# nav.net
KiCad netlist of a schematic drawn in EAGLE
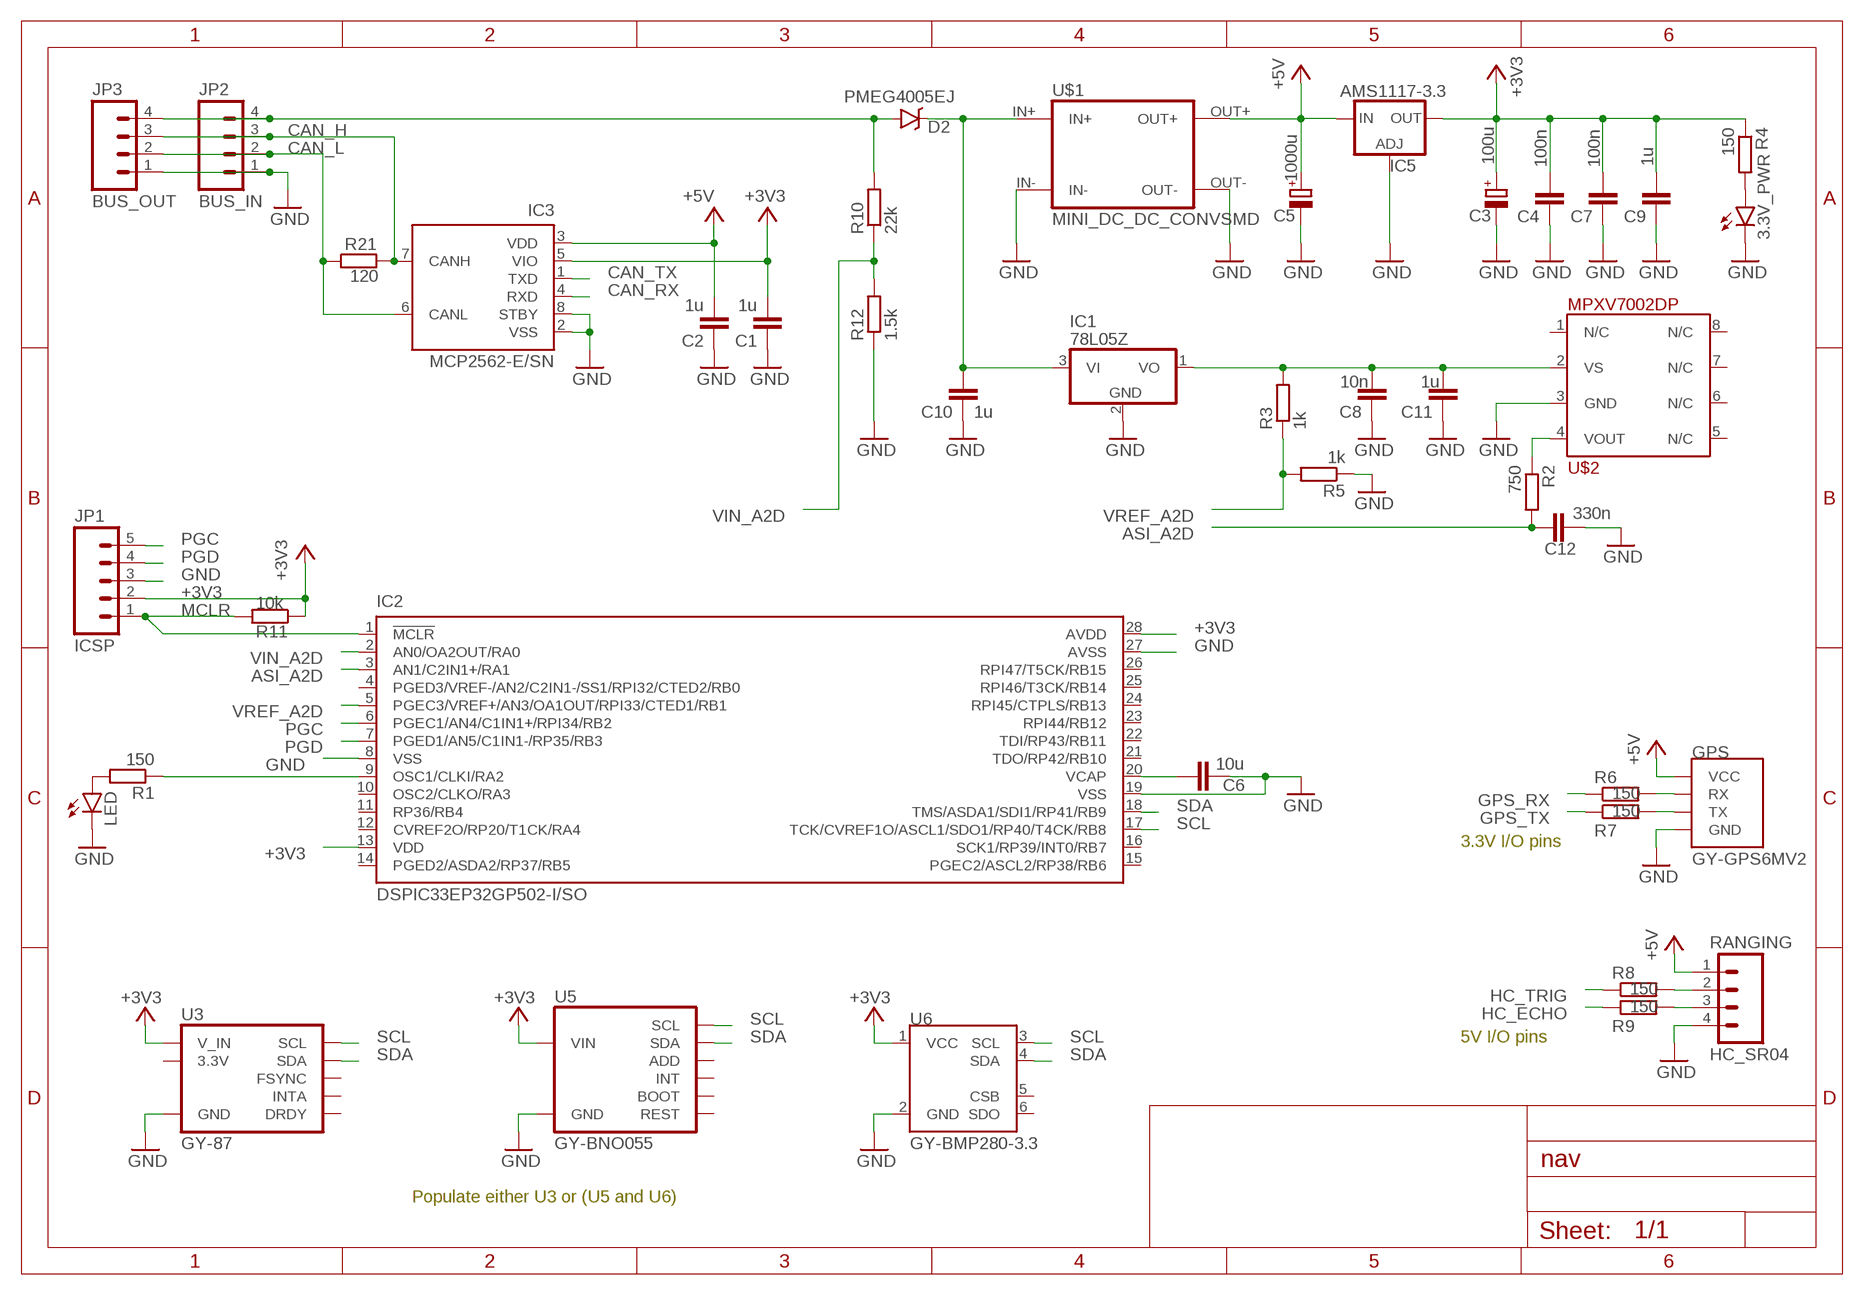
[diagram p0: schematic, sheet 1]

(export (version "E")
  (design (tool "Eeschema 10.0.6"))
  (components
    (comp (ref "3.3V_PWR")
      (value "LED-FKIT-1206")
      (footprint "eagle-import:FKIT-LED-1206")
      (libsource (lib "eagle-import") (part "LED-FKIT-1206"))
    )
    (comp (ref "C1")
      (value "1u")
      (footprint "eagle-import:C0603K")
      (libsource (lib "eagle-import") (part "C-EUC0603K"))
    )
    (comp (ref "C2")
      (value "1u")
      (footprint "eagle-import:C0603K")
      (libsource (lib "eagle-import") (part "C-EUC0603K"))
    )
    (comp (ref "C3")
      (value "100u")
      (footprint "eagle-import:E2,5-7")
      (libsource (lib "eagle-import") (part "CPOL-EUE2.5-7"))
    )
    (comp (ref "C4")
      (value "100n")
      (footprint "eagle-import:C0603K")
      (libsource (lib "eagle-import") (part "C-EUC0603K"))
    )
    (comp (ref "C5")
      (value "1000u")
      (footprint "eagle-import:E3,5-8")
      (libsource (lib "eagle-import") (part "CPOL-EUE3.5-8"))
    )
    (comp (ref "C6")
      (value "10u")
      (footprint "eagle-import:C0805K")
      (libsource (lib "eagle-import") (part "C-EUC0805K"))
    )
    (comp (ref "C7")
      (value "100n")
      (footprint "eagle-import:C0603K")
      (libsource (lib "eagle-import") (part "C-EUC0603K"))
    )
    (comp (ref "C8")
      (value "10n")
      (footprint "eagle-import:C0603K")
      (libsource (lib "eagle-import") (part "C-EUC0603K"))
    )
    (comp (ref "C9")
      (value "1u")
      (footprint "eagle-import:C0603")
      (libsource (lib "eagle-import") (part "C-EUC0603"))
    )
    (comp (ref "C10")
      (value "1u")
      (footprint "eagle-import:C0603")
      (libsource (lib "eagle-import") (part "C-EUC0603"))
    )
    (comp (ref "C11")
      (value "1u")
      (footprint "eagle-import:C0603K")
      (libsource (lib "eagle-import") (part "C-EUC0603K"))
    )
    (comp (ref "C12")
      (value "330n")
      (footprint "eagle-import:C0603K")
      (libsource (lib "eagle-import") (part "C-EUC0603K"))
    )
    (comp (ref "D2")
      (value "PMEG4005EJ")
      (footprint "eagle-import:SOD-323")
      (libsource (lib "eagle-import") (part "DIODE-SCHOTTKY-PMEG4005EJ"))
    )
    (comp (ref "GPS")
      (value "GY-GPS6MV2")
      (footprint "eagle-import:GY-GPS6MV2")
      (libsource (lib "eagle-import") (part "GY-GPS6MV2"))
    )
    (comp (ref "IC1")
      (value "78L05Z")
      (footprint "eagle-import:TO92")
      (libsource (lib "eagle-import") (part "78ZL05"))
    )
    (comp (ref "IC2")
      (value "DSPIC33EP32GP502-I/SO")
      (footprint "eagle-import:SO28W")
      (libsource (lib "eagle-import") (part "DSPIC33EP502?-I/SO32GP"))
    )
    (comp (ref "IC3")
      (value "MCP2562-E/SN")
      (footprint "eagle-import:SO-08")
      (libsource (lib "eagle-import") (part "MCP2562-E/SN"))
    )
    (comp (ref "IC5")
      (value "AMS1117-3.3")
      (footprint "eagle-import:SOT223")
      (libsource (lib "eagle-import") (part "LD117A?S33TR"))
    )
    (comp (ref "JP1")
      (value "ICSP")
      (footprint "eagle-import:1X05")
      (libsource (lib "eagle-import") (part "M05PTH"))
    )
    (comp (ref "JP2")
      (value "BUS_IN")
      (footprint "eagle-import:1X04")
      (libsource (lib "eagle-import") (part "M04PTH"))
    )
    (comp (ref "JP3")
      (value "BUS_OUT")
      (footprint "eagle-import:1X04")
      (libsource (lib "eagle-import") (part "M04PTH"))
    )
    (comp (ref "LED")
      (value "LED-FKIT-1206")
      (footprint "eagle-import:FKIT-LED-1206")
      (libsource (lib "eagle-import") (part "LED-FKIT-1206"))
    )
    (comp (ref "R1")
      (value "150")
      (footprint "eagle-import:R0603")
      (libsource (lib "eagle-import") (part "R-EU_R0603"))
    )
    (comp (ref "R2")
      (value "750")
      (footprint "eagle-import:R0603")
      (libsource (lib "eagle-import") (part "R-EU_R0603"))
    )
    (comp (ref "R3")
      (value "1k")
      (footprint "eagle-import:R0603")
      (libsource (lib "eagle-import") (part "R-EU_R0603"))
    )
    (comp (ref "R4")
      (value "150")
      (footprint "eagle-import:R0603")
      (libsource (lib "eagle-import") (part "R-EU_R0603"))
    )
    (comp (ref "R5")
      (value "1k")
      (footprint "eagle-import:R0603")
      (libsource (lib "eagle-import") (part "R-EU_R0603"))
    )
    (comp (ref "R6")
      (value "150")
      (footprint "eagle-import:R0603")
      (libsource (lib "eagle-import") (part "R-EU_R0603"))
    )
    (comp (ref "R7")
      (value "150")
      (footprint "eagle-import:R0603")
      (libsource (lib "eagle-import") (part "R-EU_R0603"))
    )
    (comp (ref "R8")
      (value "150")
      (footprint "eagle-import:R0603")
      (libsource (lib "eagle-import") (part "R-EU_R0603"))
    )
    (comp (ref "R9")
      (value "150")
      (footprint "eagle-import:R0603")
      (libsource (lib "eagle-import") (part "R-EU_R0603"))
    )
    (comp (ref "R10")
      (value "22k")
      (footprint "eagle-import:R0603")
      (libsource (lib "eagle-import") (part "R-EU_R0603"))
    )
    (comp (ref "R11")
      (value "10k")
      (footprint "eagle-import:R0603")
      (libsource (lib "eagle-import") (part "R-EU_R0603"))
    )
    (comp (ref "R12")
      (value "1.5k")
      (footprint "eagle-import:R0603")
      (libsource (lib "eagle-import") (part "R-EU_R0603"))
    )
    (comp (ref "R21")
      (value "120")
      (footprint "eagle-import:R0603")
      (libsource (lib "eagle-import") (part "R-EU_R0603"))
    )
    (comp (ref "RANGING")
      (value "HC_SR04")
      (footprint "eagle-import:1X04")
      (libsource (lib "eagle-import") (part "M04PTH"))
    )
    (comp (ref "U$1")
      (value "MINI_DC_DC_CONVSMD")
      (footprint "eagle-import:DSN-MINI-360-SMD")
      (libsource (lib "eagle-import") (part "MINI_DC_DC_CONVSMD"))
    )
    (comp (ref "U$2")
      (value "MPXV7002DP")
      (footprint "eagle-import:MPXV7002DP")
      (libsource (lib "eagle-import") (part "MPXV7002DP"))
    )
    (comp (ref "U3")
      (value "GY-87")
      (footprint "eagle-import:GY-87")
      (libsource (lib "eagle-import") (part "GY-87"))
    )
    (comp (ref "U5")
      (value "GY-BNO055")
      (footprint "eagle-import:GY-BNO055")
      (libsource (lib "eagle-import") (part "GY-BNO055"))
    )
    (comp (ref "U6")
      (value "GY-BMP280-3.3")
      (footprint "eagle-import:GY-BMP280-3.3")
      (libsource (lib "eagle-import") (part "GY-BMP280-3.3"))
    )
  )
  (nets
    (net (code "1") (name "+3V3") (class "Default")
      (node (ref "C1") (pin "2") (pinfunction "2_2") (pintype "passive"))
      (node (ref "C3") (pin "+") (pinfunction "+_+") (pintype "passive"))
      (node (ref "C4") (pin "2") (pinfunction "2_2") (pintype "passive"))
      (node (ref "C7") (pin "2") (pinfunction "2_2") (pintype "passive"))
      (node (ref "C9") (pin "2") (pinfunction "2_2") (pintype "passive"))
      (node (ref "IC2") (pin "13") (pinfunction "VDD_13") (pintype "power_in"))
      (node (ref "IC2") (pin "28") (pinfunction "AVDD_28") (pintype "power_in"))
      (node (ref "IC3") (pin "5") (pinfunction "VIO_5") (pintype "power_in"))
      (node (ref "IC5") (pin "2") (pinfunction "OUT_2") (pintype "passive"))
      (node (ref "IC5") (pin "@2") (pinfunction "OUT_@2") (pintype "passive"))
      (node (ref "JP1") (pin "2") (pinfunction "2_2") (pintype "passive"))
      (node (ref "R11") (pin "1") (pinfunction "1_1") (pintype "passive"))
      (node (ref "R4") (pin "1") (pinfunction "1_1") (pintype "passive"))
      (node (ref "U3") (pin "VCC_IN") (pinfunction "V_IN_VCC_IN") (pintype "power_in"))
      (node (ref "U5") (pin "VIN") (pinfunction "VIN_VIN") (pintype "power_in"))
      (node (ref "U6") (pin "1") (pinfunction "VCC_1") (pintype "bidirectional"))
    )
    (net (code "2") (name "+5V") (class "Default")
      (node (ref "C2") (pin "2") (pinfunction "2_2") (pintype "passive"))
      (node (ref "C5") (pin "+") (pinfunction "+_+") (pintype "passive"))
      (node (ref "GPS") (pin "VCC") (pinfunction "VCC_VCC") (pintype "power_in"))
      (node (ref "IC3") (pin "3") (pinfunction "VDD_3") (pintype "power_in"))
      (node (ref "IC5") (pin "3") (pinfunction "IN_3") (pintype "input"))
      (node (ref "RANGING") (pin "1") (pinfunction "1_1") (pintype "passive"))
      (node (ref "U$1") (pin "OUT+") (pinfunction "OUT+_OUT+") (pintype "output"))
    )
    (net (code "3") (name "/3.3V") (class "Default")
      (node (ref "U3") (pin "3.3V") (pinfunction "3.3V_3.3V") (pintype "power_in"))
    )
    (net (code "4") (name "/ASI_A2D") (class "Default")
      (node (ref "C12") (pin "2") (pinfunction "2_2") (pintype "passive"))
      (node (ref "IC2") (pin "3") (pinfunction "AN1/C2IN1+/RA1_3") (pintype "bidirectional"))
      (node (ref "R2") (pin "2") (pinfunction "2_2") (pintype "passive"))
    )
    (net (code "5") (name "/CAN_H") (class "Default")
      (node (ref "IC3") (pin "7") (pinfunction "CANH_7") (pintype "bidirectional"))
      (node (ref "JP2") (pin "3") (pinfunction "3_3") (pintype "passive"))
      (node (ref "JP3") (pin "3") (pinfunction "3_3") (pintype "passive"))
      (node (ref "R21") (pin "2") (pinfunction "2_2") (pintype "passive"))
    )
    (net (code "6") (name "/CAN_L") (class "Default")
      (node (ref "IC3") (pin "6") (pinfunction "CANL_6") (pintype "bidirectional"))
      (node (ref "JP2") (pin "2") (pinfunction "2_2") (pintype "passive"))
      (node (ref "JP3") (pin "2") (pinfunction "2_2") (pintype "passive"))
      (node (ref "R21") (pin "1") (pinfunction "1_1") (pintype "passive"))
    )
    (net (code "7") (name "/CAN_RX") (class "Default")
      (node (ref "IC3") (pin "4") (pinfunction "RXD_4") (pintype "output"))
    )
    (net (code "8") (name "/CAN_TX") (class "Default")
      (node (ref "IC3") (pin "1") (pinfunction "TXD_1") (pintype "input"))
    )
    (net (code "9") (name "/GPS_RX") (class "Default")
      (node (ref "R6") (pin "1") (pinfunction "1_1") (pintype "passive"))
    )
    (net (code "10") (name "/GPS_TX") (class "Default")
      (node (ref "R7") (pin "1") (pinfunction "1_1") (pintype "passive"))
    )
    (net (code "11") (name "/HC_ECHO") (class "Default")
      (node (ref "R9") (pin "1") (pinfunction "1_1") (pintype "passive"))
    )
    (net (code "12") (name "/HC_TRIG") (class "Default")
      (node (ref "R8") (pin "1") (pinfunction "1_1") (pintype "passive"))
    )
    (net (code "13") (name "/MCLR") (class "Default")
      (node (ref "IC2") (pin "1") (pinfunction "~{MCLR}_1") (pintype "input"))
      (node (ref "JP1") (pin "1") (pinfunction "1_1") (pintype "passive"))
      (node (ref "R11") (pin "2") (pinfunction "2_2") (pintype "passive"))
    )
    (net (code "14") (name "/PGC") (class "Default")
      (node (ref "IC2") (pin "6") (pinfunction "PGEC1/AN4/C1IN1+/RPI34/RB2_6") (pintype "bidirectional"))
      (node (ref "JP1") (pin "5") (pinfunction "5_5") (pintype "passive"))
    )
    (net (code "15") (name "/PGD") (class "Default")
      (node (ref "IC2") (pin "7") (pinfunction "PGED1/AN5/C1IN1-/RP35/RB3_7") (pintype "bidirectional"))
      (node (ref "JP1") (pin "4") (pinfunction "4_4") (pintype "passive"))
    )
    (net (code "16") (name "/SCL") (class "Default")
      (node (ref "IC2") (pin "17") (pinfunction "TCK/CVREF1O/ASCL1/SDO1/RP40/T4CK/RB8_17") (pintype "bidirectional"))
      (node (ref "U3") (pin "SCL") (pinfunction "SCL_SCL") (pintype "bidirectional"))
      (node (ref "U5") (pin "SCL") (pinfunction "SCL_SCL") (pintype "input"))
      (node (ref "U6") (pin "3") (pinfunction "SCL_3") (pintype "bidirectional"))
    )
    (net (code "17") (name "/SDA") (class "Default")
      (node (ref "IC2") (pin "18") (pinfunction "TMS/ASDA1/SDI1/RP41/RB9_18") (pintype "bidirectional"))
      (node (ref "U3") (pin "SDA") (pinfunction "SDA_SDA") (pintype "bidirectional"))
      (node (ref "U5") (pin "SDA") (pinfunction "SDA_SDA") (pintype "bidirectional"))
      (node (ref "U6") (pin "4") (pinfunction "SDA_4") (pintype "bidirectional"))
    )
    (net (code "18") (name "/VIN_A2D") (class "Default")
      (node (ref "IC2") (pin "2") (pinfunction "AN0/OA2OUT/RA0_2") (pintype "bidirectional"))
      (node (ref "R10") (pin "1") (pinfunction "1_1") (pintype "passive"))
      (node (ref "R12") (pin "2") (pinfunction "2_2") (pintype "passive"))
    )
    (net (code "19") (name "/VREF_A2D") (class "Default")
      (node (ref "IC2") (pin "5") (pinfunction "PGEC3/VREF+/AN3/OA1OUT/RPI33/CTED1/RB1_5") (pintype "bidirectional"))
      (node (ref "R3") (pin "1") (pinfunction "1_1") (pintype "passive"))
      (node (ref "R5") (pin "2") (pinfunction "2_2") (pintype "passive"))
    )
    (net (code "20") (name "GND") (class "Default")
      (node (ref "3.3V_PWR") (pin "C") (pinfunction "C_C") (pintype "passive"))
      (node (ref "C1") (pin "1") (pinfunction "1_1") (pintype "passive"))
      (node (ref "C10") (pin "1") (pinfunction "1_1") (pintype "passive"))
      (node (ref "C11") (pin "1") (pinfunction "1_1") (pintype "passive"))
      (node (ref "C12") (pin "1") (pinfunction "1_1") (pintype "passive"))
      (node (ref "C2") (pin "1") (pinfunction "1_1") (pintype "passive"))
      (node (ref "C3") (pin "-") (pinfunction "-_-") (pintype "passive"))
      (node (ref "C4") (pin "1") (pinfunction "1_1") (pintype "passive"))
      (node (ref "C5") (pin "-") (pinfunction "-_-") (pintype "passive"))
      (node (ref "C6") (pin "1") (pinfunction "1_1") (pintype "passive"))
      (node (ref "C7") (pin "1") (pinfunction "1_1") (pintype "passive"))
      (node (ref "C8") (pin "1") (pinfunction "1_1") (pintype "passive"))
      (node (ref "C9") (pin "1") (pinfunction "1_1") (pintype "passive"))
      (node (ref "GPS") (pin "GND") (pinfunction "GND_GND") (pintype "power_in"))
      (node (ref "IC1") (pin "2") (pinfunction "GND_2") (pintype "passive"))
      (node (ref "IC2") (pin "19") (pinfunction "VSS_19") (pintype "power_in"))
      (node (ref "IC2") (pin "27") (pinfunction "AVSS_27") (pintype "power_in"))
      (node (ref "IC2") (pin "8") (pinfunction "VSS_8") (pintype "power_in"))
      (node (ref "IC3") (pin "2") (pinfunction "VSS_2") (pintype "power_in"))
      (node (ref "IC3") (pin "8") (pinfunction "STBY_8") (pintype "input"))
      (node (ref "IC5") (pin "1") (pinfunction "ADJ_1") (pintype "input"))
      (node (ref "JP1") (pin "3") (pinfunction "3_3") (pintype "passive"))
      (node (ref "JP2") (pin "1") (pinfunction "1_1") (pintype "passive"))
      (node (ref "JP3") (pin "1") (pinfunction "1_1") (pintype "passive"))
      (node (ref "LED") (pin "C") (pinfunction "C_C") (pintype "passive"))
      (node (ref "R12") (pin "1") (pinfunction "1_1") (pintype "passive"))
      (node (ref "R5") (pin "1") (pinfunction "1_1") (pintype "passive"))
      (node (ref "RANGING") (pin "4") (pinfunction "4_4") (pintype "passive"))
      (node (ref "U$1") (pin "IN-") (pinfunction "IN-_IN-") (pintype "power_in"))
      (node (ref "U$1") (pin "OUT-") (pinfunction "OUT-_OUT-") (pintype "power_in"))
      (node (ref "U$2") (pin "3") (pinfunction "GND_3") (pintype "bidirectional"))
      (node (ref "U3") (pin "GND") (pinfunction "GND_GND") (pintype "power_in"))
      (node (ref "U5") (pin "GND") (pinfunction "GND_GND") (pintype "power_in"))
      (node (ref "U6") (pin "2") (pinfunction "GND_2") (pintype "bidirectional"))
    )
    (net (code "21") (name "Net-(3.3V_PWR-PadA)") (class "Default")
      (node (ref "3.3V_PWR") (pin "A") (pinfunction "A_A") (pintype "passive"))
      (node (ref "R4") (pin "2") (pinfunction "2_2") (pintype "passive"))
    )
    (net (code "22") (name "Net-(D2-PadA)") (class "Default")
      (node (ref "D2") (pin "A") (pinfunction "A_A") (pintype "passive"))
      (node (ref "JP2") (pin "4") (pinfunction "4_4") (pintype "passive"))
      (node (ref "JP3") (pin "4") (pinfunction "4_4") (pintype "passive"))
      (node (ref "R10") (pin "2") (pinfunction "2_2") (pintype "passive"))
    )
    (net (code "23") (name "Net-(GPS-PadRX)") (class "Default")
      (node (ref "GPS") (pin "RX") (pinfunction "RX_RX") (pintype "input"))
      (node (ref "R6") (pin "2") (pinfunction "2_2") (pintype "passive"))
    )
    (net (code "24") (name "Net-(GPS-PadTX)") (class "Default")
      (node (ref "GPS") (pin "TX") (pinfunction "TX_TX") (pintype "output"))
      (node (ref "R7") (pin "2") (pinfunction "2_2") (pintype "passive"))
    )
    (net (code "25") (name "Net-(IC1-VI)") (class "Default")
      (node (ref "C10") (pin "2") (pinfunction "2_2") (pintype "passive"))
      (node (ref "D2") (pin "C") (pinfunction "C_C") (pintype "passive"))
      (node (ref "IC1") (pin "3") (pinfunction "VI_3") (pintype "input"))
      (node (ref "U$1") (pin "IN+") (pinfunction "IN+_IN+") (pintype "input"))
    )
    (net (code "26") (name "Net-(IC1-VO)") (class "Default")
      (node (ref "C11") (pin "2") (pinfunction "2_2") (pintype "passive"))
      (node (ref "C8") (pin "2") (pinfunction "2_2") (pintype "passive"))
      (node (ref "IC1") (pin "1") (pinfunction "VO_1") (pintype "passive"))
      (node (ref "R3") (pin "2") (pinfunction "2_2") (pintype "passive"))
      (node (ref "U$2") (pin "2") (pinfunction "VS_2") (pintype "bidirectional"))
    )
    (net (code "27") (name "Net-(IC2-OSC1{slash}CLKI{slash}RA2)") (class "Default")
      (node (ref "IC2") (pin "9") (pinfunction "OSC1/CLKI/RA2_9") (pintype "input"))
      (node (ref "R1") (pin "1") (pinfunction "1_1") (pintype "passive"))
    )
    (net (code "28") (name "Net-(IC2-VCAP)") (class "Default")
      (node (ref "C6") (pin "2") (pinfunction "2_2") (pintype "passive"))
      (node (ref "IC2") (pin "20") (pinfunction "VCAP_20") (pintype "power_in"))
    )
    (net (code "29") (name "Net-(LED-PadA)") (class "Default")
      (node (ref "LED") (pin "A") (pinfunction "A_A") (pintype "passive"))
      (node (ref "R1") (pin "2") (pinfunction "2_2") (pintype "passive"))
    )
    (net (code "30") (name "Net-(R8-Pad2)") (class "Default")
      (node (ref "R8") (pin "2") (pinfunction "2_2") (pintype "passive"))
      (node (ref "RANGING") (pin "2") (pinfunction "2_2") (pintype "passive"))
    )
    (net (code "31") (name "Net-(R9-Pad2)") (class "Default")
      (node (ref "R9") (pin "2") (pinfunction "2_2") (pintype "passive"))
      (node (ref "RANGING") (pin "3") (pinfunction "3_3") (pintype "passive"))
    )
    (net (code "32") (name "Net-(U$2-VOUT)") (class "Default")
      (node (ref "R2") (pin "1") (pinfunction "1_1") (pintype "passive"))
      (node (ref "U$2") (pin "4") (pinfunction "VOUT_4") (pintype "bidirectional"))
    )
    (net (code "33") (name "unconnected-(IC2-CVREF2O{slash}RP20{slash}T1CK{slash}RA4-Pad12)") (class "Default")
      (node (ref "IC2") (pin "12") (pinfunction "CVREF2O/RP20/T1CK/RA4_12") (pintype "bidirectional"))
    )
    (net (code "34") (name "unconnected-(IC2-OSC2{slash}CLKO{slash}RA3-Pad10)") (class "Default")
      (node (ref "IC2") (pin "10") (pinfunction "OSC2/CLKO/RA3_10") (pintype "bidirectional"))
    )
    (net (code "35") (name "unconnected-(IC2-PGEC2{slash}ASCL2{slash}RP38{slash}RB6-Pad15)") (class "Default")
      (node (ref "IC2") (pin "15") (pinfunction "PGEC2/ASCL2/RP38/RB6_15") (pintype "bidirectional"))
    )
    (net (code "36") (name "unconnected-(IC2-PGED2{slash}ASDA2{slash}RP37{slash}RB5-Pad14)") (class "Default")
      (node (ref "IC2") (pin "14") (pinfunction "PGED2/ASDA2/RP37/RB5_14") (pintype "bidirectional"))
    )
    (net (code "37") (name "unconnected-(IC2-PGED3{slash}VREF-{slash}AN2{slash}C2IN1-{slash}SS1{slash}RPI32{slash}CTED2{slash}RB0-Pad4)") (class "Default")
      (node (ref "IC2") (pin "4") (pinfunction "PGED3/VREF-/AN2/C2IN1-/SS1/RPI32/CTED2/RB0_4") (pintype "bidirectional"))
    )
    (net (code "38") (name "unconnected-(IC2-RP36{slash}RB4-Pad11)") (class "Default")
      (node (ref "IC2") (pin "11") (pinfunction "RP36/RB4_11") (pintype "bidirectional"))
    )
    (net (code "39") (name "unconnected-(IC2-RPI44{slash}RB12-Pad23)") (class "Default")
      (node (ref "IC2") (pin "23") (pinfunction "RPI44/RB12_23") (pintype "bidirectional"))
    )
    (net (code "40") (name "unconnected-(IC2-RPI45{slash}CTPLS{slash}RB13-Pad24)") (class "Default")
      (node (ref "IC2") (pin "24") (pinfunction "RPI45/CTPLS/RB13_24") (pintype "bidirectional"))
    )
    (net (code "41") (name "unconnected-(IC2-RPI46{slash}T3CK{slash}RB14-Pad25)") (class "Default")
      (node (ref "IC2") (pin "25") (pinfunction "RPI46/T3CK/RB14_25") (pintype "bidirectional"))
    )
    (net (code "42") (name "unconnected-(IC2-RPI47{slash}T5CK{slash}RB15-Pad26)") (class "Default")
      (node (ref "IC2") (pin "26") (pinfunction "RPI47/T5CK/RB15_26") (pintype "bidirectional"))
    )
    (net (code "43") (name "unconnected-(IC2-SCK1{slash}RP39{slash}INT0{slash}RB7-Pad16)") (class "Default")
      (node (ref "IC2") (pin "16") (pinfunction "SCK1/RP39/INT0/RB7_16") (pintype "bidirectional"))
    )
    (net (code "44") (name "unconnected-(IC2-TDI{slash}RP43{slash}RB11-Pad22)") (class "Default")
      (node (ref "IC2") (pin "22") (pinfunction "TDI/RP43/RB11_22") (pintype "bidirectional"))
    )
    (net (code "45") (name "unconnected-(IC2-TDO{slash}RP42{slash}RB10-Pad21)") (class "Default")
      (node (ref "IC2") (pin "21") (pinfunction "TDO/RP42/RB10_21") (pintype "bidirectional"))
    )
    (net (code "46") (name "unconnected-(U$2-N{slash}C-Pad1)") (class "Default")
      (node (ref "U$2") (pin "1") (pinfunction "N/C_1") (pintype "bidirectional"))
    )
    (net (code "47") (name "unconnected-(U$2-N{slash}C-Pad5)") (class "Default")
      (node (ref "U$2") (pin "5") (pinfunction "N/C_5") (pintype "bidirectional"))
    )
    (net (code "48") (name "unconnected-(U$2-N{slash}C-Pad6)") (class "Default")
      (node (ref "U$2") (pin "6") (pinfunction "N/C_6") (pintype "bidirectional"))
    )
    (net (code "49") (name "unconnected-(U$2-N{slash}C-Pad7)") (class "Default")
      (node (ref "U$2") (pin "7") (pinfunction "N/C_7") (pintype "bidirectional"))
    )
    (net (code "50") (name "unconnected-(U$2-N{slash}C-Pad8)") (class "Default")
      (node (ref "U$2") (pin "8") (pinfunction "N/C_8") (pintype "bidirectional"))
    )
    (net (code "51") (name "unconnected-(U3-PadDRDY)") (class "Default")
      (node (ref "U3") (pin "DRDY") (pinfunction "DRDY_DRDY") (pintype "output"))
    )
    (net (code "52") (name "unconnected-(U3-PadFSYNC)") (class "Default")
      (node (ref "U3") (pin "FSYNC") (pinfunction "FSYNC_FSYNC") (pintype "output"))
    )
    (net (code "53") (name "unconnected-(U3-PadINTA)") (class "Default")
      (node (ref "U3") (pin "INTA") (pinfunction "INTA_INTA") (pintype "output"))
    )
    (net (code "54") (name "unconnected-(U5-PadADD)") (class "Default")
      (node (ref "U5") (pin "ADD") (pinfunction "ADD_ADD") (pintype "input"))
    )
    (net (code "55") (name "unconnected-(U5-PadBOOT)") (class "Default")
      (node (ref "U5") (pin "BOOT") (pinfunction "BOOT_BOOT") (pintype "input"))
    )
    (net (code "56") (name "unconnected-(U5-PadINT)") (class "Default")
      (node (ref "U5") (pin "INT") (pinfunction "INT_INT") (pintype "output"))
    )
    (net (code "57") (name "unconnected-(U5-PadREST)") (class "Default")
      (node (ref "U5") (pin "REST") (pinfunction "REST_REST") (pintype "input"))
    )
    (net (code "58") (name "unconnected-(U6-CSB-Pad5)") (class "Default")
      (node (ref "U6") (pin "5") (pinfunction "CSB_5") (pintype "bidirectional"))
    )
    (net (code "59") (name "unconnected-(U6-SDO-Pad6)") (class "Default")
      (node (ref "U6") (pin "6") (pinfunction "SDO_6") (pintype "bidirectional"))
    )
  )
)
